# passive_A-B_box.net
KiCad netlist of a schematic drawn in EAGLE
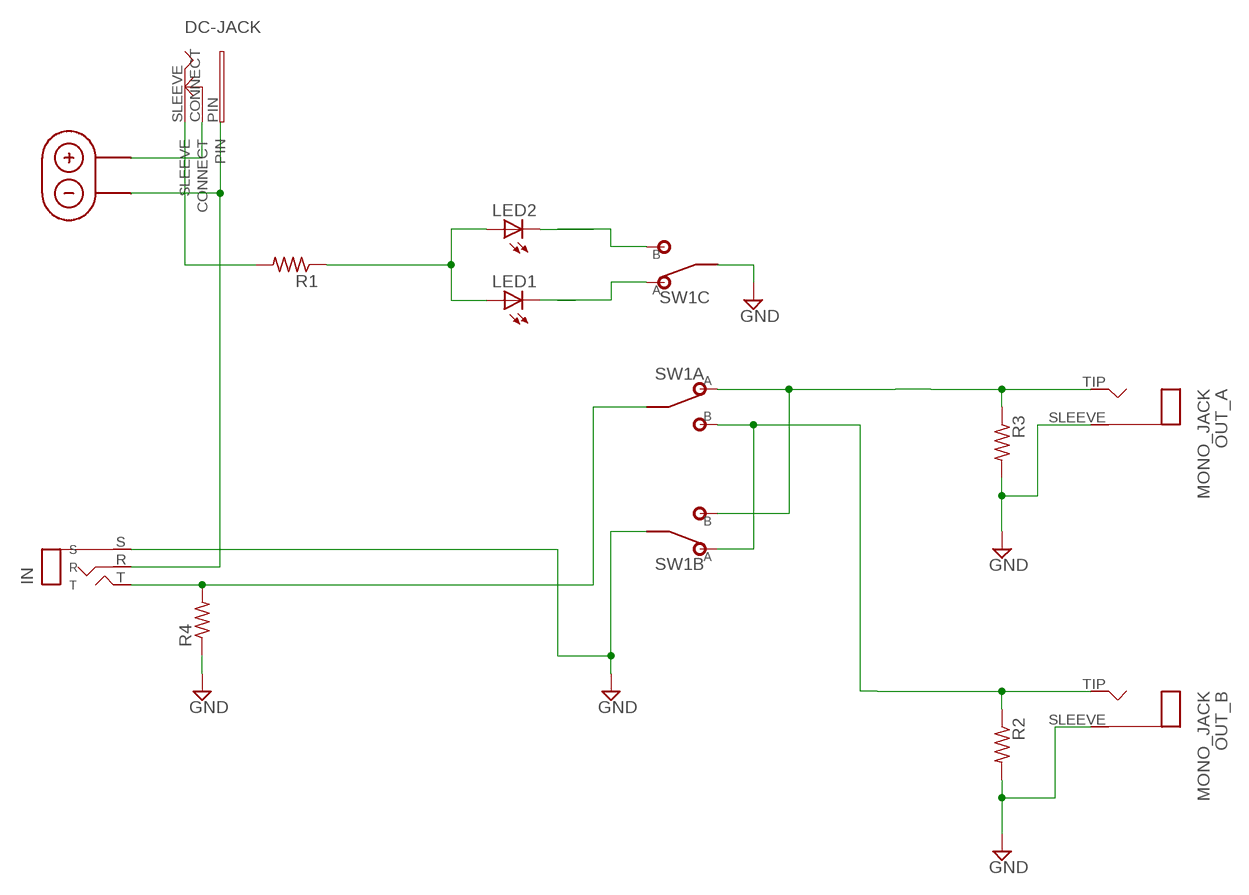
[diagram p0: schematic, sheet 1]

(export (version "E")
  (design (tool "Eeschema 10.0.6"))
  (components
    (comp (ref "DC-JACK")
      (value "DC_JACK")
      (footprint "eagle-import:DC_JACK_OFFBOARD")
      (libsource (lib "eagle-import") (part "DC_JACK_OFFBOARD"))
    )
    (comp (ref "IN")
      (value "STEREO_JACK")
      (footprint "eagle-import:STEREO_JACK")
      (libsource (lib "eagle-import") (part "STEREO_JACK"))
    )
    (comp (ref "LED1")
      (value "LED5MM")
      (footprint "eagle-import:LED5MM")
      (libsource (lib "eagle-import") (part "LED5MM"))
    )
    (comp (ref "LED2")
      (value "LED5MM")
      (footprint "eagle-import:LED5MM")
      (libsource (lib "eagle-import") (part "LED5MM"))
    )
    (comp (ref "OUT_A")
      (value "MONO_JACK")
      (footprint "eagle-import:MONO_JACK")
      (libsource (lib "eagle-import") (part "MONO_JACK"))
    )
    (comp (ref "OUT_B")
      (value "MONO_JACK")
      (footprint "eagle-import:MONO_JACK")
      (libsource (lib "eagle-import") (part "MONO_JACK"))
    )
    (comp (ref "R1")
      (value "RESISTOR")
      (footprint "eagle-import:RESISTOR")
      (libsource (lib "eagle-import") (part "RESISTOR"))
    )
    (comp (ref "R2")
      (value "RESISTOR")
      (footprint "eagle-import:RESISTOR")
      (libsource (lib "eagle-import") (part "RESISTOR"))
    )
    (comp (ref "R3")
      (value "RESISTOR")
      (footprint "eagle-import:RESISTOR")
      (libsource (lib "eagle-import") (part "RESISTOR"))
    )
    (comp (ref "R4")
      (value "RESISTOR")
      (footprint "eagle-import:RESISTOR")
      (libsource (lib "eagle-import") (part "RESISTOR"))
    )
    (comp (ref "SW1")
      (value "3PDT")
      (footprint "eagle-import:3PDT")
      (libsource (lib "eagle-import") (part "3PDT"))
    )
    (comp (ref "U$4")
      (value "9V_BATTERY_CLIP")
      (footprint "eagle-import:9V_BATTERY")
      (libsource (lib "eagle-import") (part "9V_BATTERY_CLIP"))
    )
  )
  (nets
    (net (code "1") (name "GND") (class "Default")
      (node (ref "IN") (pin "S") (pinfunction "S_S") (pintype "passive"))
      (node (ref "OUT_A") (pin "SLEEVE") (pinfunction "SLEEVE_SLEEVE") (pintype "passive"))
      (node (ref "OUT_B") (pin "SLEEVE") (pinfunction "SLEEVE_SLEEVE") (pintype "passive"))
      (node (ref "R2") (pin "2") (pinfunction "2_2") (pintype "passive"))
      (node (ref "R3") (pin "2") (pinfunction "2_2") (pintype "passive"))
      (node (ref "R4") (pin "1") (pinfunction "1_1") (pintype "passive"))
      (node (ref "SW1") (pin "B2") (pinfunction "COM_B2") (pintype "passive"))
      (node (ref "SW1") (pin "C2") (pinfunction "COM_C2") (pintype "passive"))
    )
    (net (code "2") (name "Net-(DC-JACK-PadCONNECT)") (class "Default")
      (node (ref "DC-JACK") (pin "CONNECT") (pinfunction "CONNECT_CONNECT") (pintype "bidirectional"))
      (node (ref "U$4") (pin "9V_BATTERY_+") (pinfunction "9V_BATTERY_+_9V_BATTERY_+") (pintype "power_in"))
    )
    (net (code "3") (name "Net-(DC-JACK-PadPIN)") (class "Default")
      (node (ref "DC-JACK") (pin "PIN") (pinfunction "PIN_PIN") (pintype "bidirectional"))
      (node (ref "IN") (pin "R") (pinfunction "R_R") (pintype "passive"))
      (node (ref "U$4") (pin "9V_BATTERY_-") (pinfunction "9V_BATTERY_-_9V_BATTERY_-") (pintype "power_in"))
    )
    (net (code "4") (name "Net-(DC-JACK-PadSLEEVE)") (class "Default")
      (node (ref "DC-JACK") (pin "SLEEVE") (pinfunction "SLEEVE_SLEEVE") (pintype "bidirectional"))
      (node (ref "R1") (pin "2") (pinfunction "2_2") (pintype "passive"))
    )
    (net (code "5") (name "Net-(LED1-C)") (class "Default")
      (node (ref "LED1") (pin "K") (pinfunction "C_K") (pintype "passive"))
      (node (ref "SW1") (pin "C1") (pinfunction "A_C1") (pintype "passive"))
    )
    (net (code "6") (name "Net-(LED1-PadA)") (class "Default")
      (node (ref "LED1") (pin "A") (pinfunction "A_A") (pintype "passive"))
      (node (ref "LED2") (pin "A") (pinfunction "A_A") (pintype "passive"))
      (node (ref "R1") (pin "1") (pinfunction "1_1") (pintype "passive"))
    )
    (net (code "7") (name "Net-(LED2-C)") (class "Default")
      (node (ref "LED2") (pin "K") (pinfunction "C_K") (pintype "passive"))
      (node (ref "SW1") (pin "C3") (pinfunction "B_C3") (pintype "passive"))
    )
    (net (code "8") (name "Net-(SW1A-A)") (class "Default")
      (node (ref "OUT_A") (pin "TIP") (pinfunction "TIP_TIP") (pintype "passive"))
      (node (ref "R3") (pin "1") (pinfunction "1_1") (pintype "passive"))
      (node (ref "SW1") (pin "A1") (pinfunction "A_A1") (pintype "passive"))
      (node (ref "SW1") (pin "B3") (pinfunction "B_B3") (pintype "passive"))
    )
    (net (code "9") (name "Net-(SW1A-B)") (class "Default")
      (node (ref "OUT_B") (pin "TIP") (pinfunction "TIP_TIP") (pintype "passive"))
      (node (ref "R2") (pin "1") (pinfunction "1_1") (pintype "passive"))
      (node (ref "SW1") (pin "A3") (pinfunction "B_A3") (pintype "passive"))
      (node (ref "SW1") (pin "B1") (pinfunction "A_B1") (pintype "passive"))
    )
    (net (code "10") (name "Net-(SW1A-COM)") (class "Default")
      (node (ref "IN") (pin "T") (pinfunction "T_T") (pintype "passive"))
      (node (ref "R4") (pin "2") (pinfunction "2_2") (pintype "passive"))
      (node (ref "SW1") (pin "A2") (pinfunction "COM_A2") (pintype "passive"))
    )
  )
)
